# 2_-BATTERY.net
KiCad netlist of a schematic drawn in Altium Designer
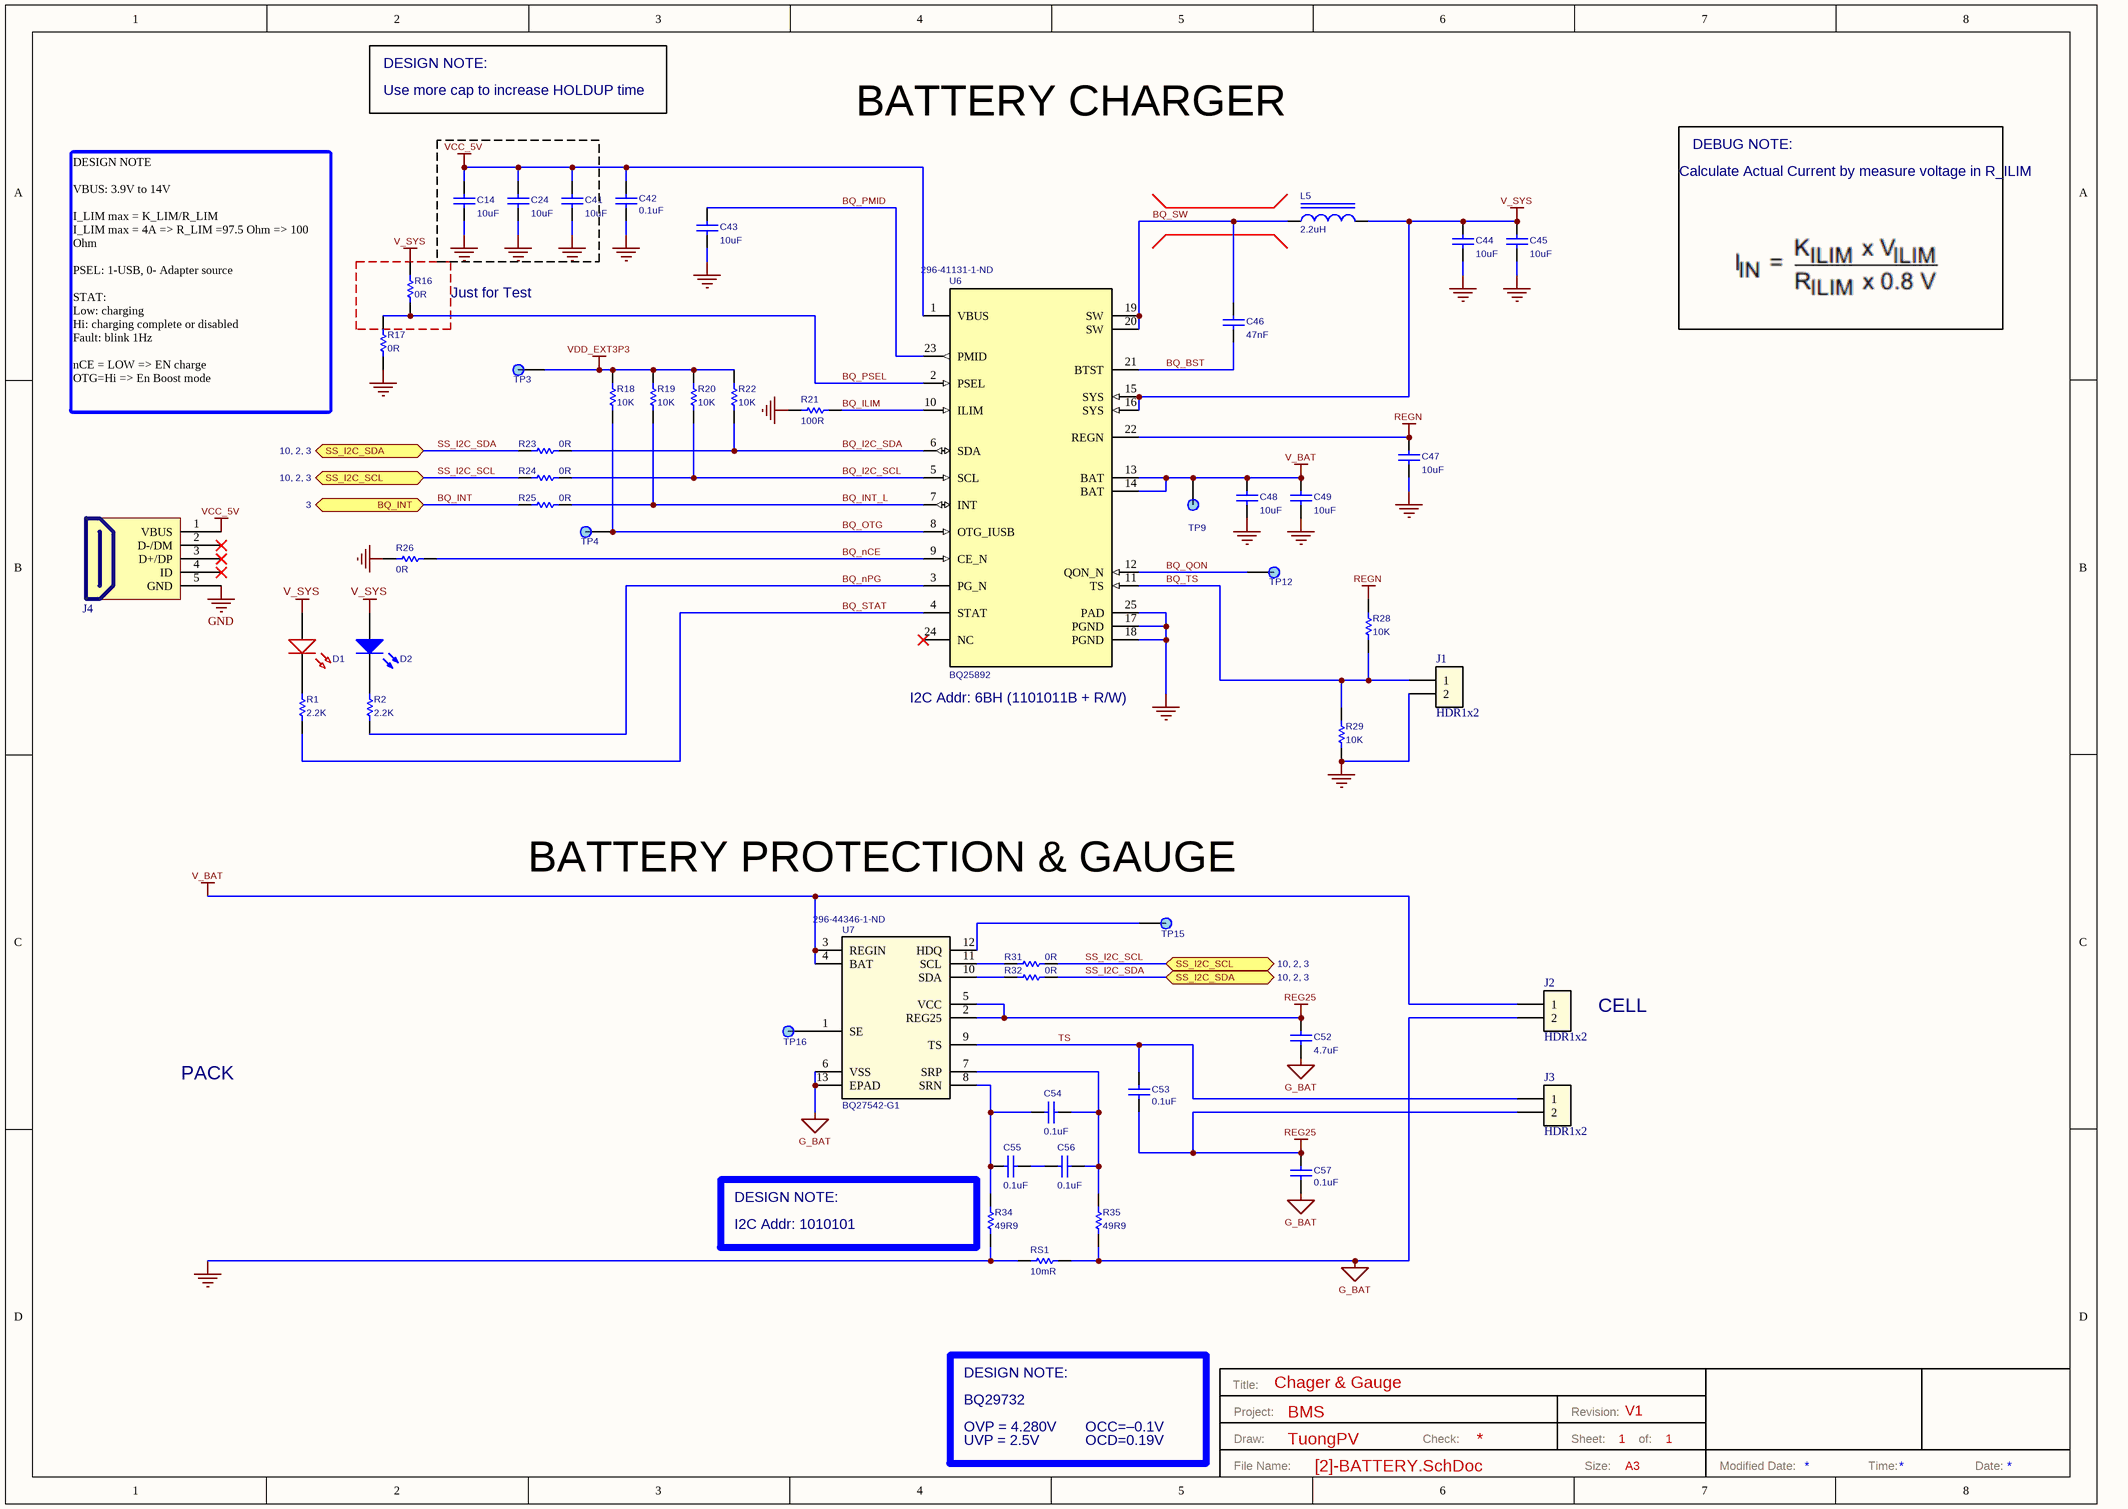
[diagram p0: [2]-BATTERY.SchDoc]

(export (version "E")
  (design (tool "Eeschema 10.0.6"))
  (components
    (comp (ref "C14")
      (value "TMK212BBJ106KG-T")
      (footprint "C0805")
      (description "CAP, CERM, 10uF, 25V, +/-10%, X5R, 0402")
      (fields
        (field (name "LUMI PART") "CAP_10uF_0805")
        (field (name "MANUFACTURER") "Taiyo Yuden")
        (field (name "CAPACITANCE") "10uF")
      )
      (libsource (lib "EFL_AltiumLib") (part "CAP_10uF_0805"))
    )
    (comp (ref "C24")
      (value "TMK212BBJ106KG-T")
      (footprint "C0805")
      (description "CAP, CERM, 10uF, 25V, +/-10%, X5R, 0402")
      (fields
        (field (name "LUMI PART") "CAP_10uF_0805")
        (field (name "MANUFACTURER") "Taiyo Yuden")
        (field (name "CAPACITANCE") "10uF")
      )
      (libsource (lib "EFL_AltiumLib") (part "CAP_10uF_0805"))
    )
    (comp (ref "C41")
      (value "TMK212BBJ106KG-T")
      (footprint "C0805")
      (description "CAP, CERM, 10uF, 25V, +/-10%, X5R, 0402")
      (fields
        (field (name "LUMI PART") "CAP_10uF_0805")
        (field (name "MANUFACTURER") "Taiyo Yuden")
        (field (name "CAPACITANCE") "10uF")
      )
      (libsource (lib "EFL_AltiumLib") (part "CAP_10uF_0805"))
    )
    (comp (ref "C42")
      (value "0603B104K500CT")
      (footprint "C0603")
      (description "CAP, CERM, 0.1uF, 50V, +/-10%, X7R, 0603")
      (fields
        (field (name "LUMI PART") "CAP_104_0603")
        (field (name "MANUFACTURER") "Walsin")
        (field (name "CAPACITANCE") "0.1uF")
      )
      (libsource (lib "LumiLib-CAPACITOR") (part "CERM_0.1uF_0603"))
    )
    (comp (ref "C43")
      (value "TMK212BBJ106KG-T")
      (footprint "C0805")
      (description "CAP, CERM, 10uF, 25V, +/-10%, X5R, 0402")
      (fields
        (field (name "LUMI PART") "CAP_10uF_0805")
        (field (name "MANUFACTURER") "Taiyo Yuden")
        (field (name "CAPACITANCE") "10uF")
      )
      (libsource (lib "EFL_AltiumLib") (part "CAP_10uF_0805"))
    )
    (comp (ref "C44")
      (value "TMK212BBJ106KG-T")
      (footprint "C0805")
      (description "CAP, CERM, 10uF, 25V, +/-10%, X5R, 0402")
      (fields
        (field (name "LUMI PART") "CAP_10uF_0805")
        (field (name "MANUFACTURER") "Taiyo Yuden")
        (field (name "CAPACITANCE") "10uF")
      )
      (libsource (lib "EFL_AltiumLib") (part "CAP_10uF_0805"))
    )
    (comp (ref "C45")
      (value "TMK212BBJ106KG-T")
      (footprint "C0805")
      (description "CAP, CERM, 10uF, 25V, +/-10%, X5R, 0402")
      (fields
        (field (name "LUMI PART") "CAP_10uF_0805")
        (field (name "MANUFACTURER") "Taiyo Yuden")
        (field (name "CAPACITANCE") "10uF")
      )
      (libsource (lib "EFL_AltiumLib") (part "CAP_10uF_0805"))
    )
    (comp (ref "C46")
      (value "GRM155R71C473KA01D")
      (footprint "C0402")
      (description "CAP, CERM, 47nF, 16V, +/-10%, X7R, 0402")
      (fields
        (field (name "LUMI PART") "CAP_47nF_0402")
        (field (name "MANUFACTURER") "Murata")
        (field (name "CAPACITANCE") "47nF")
      )
      (libsource (lib "EFL_GW") (part "CAP_47nF_0402"))
    )
    (comp (ref "C47")
      (value "TMK212BBJ106KG-T")
      (footprint "C0805")
      (description "CAP, CERM, 10uF, 25V, +/-10%, X5R, 0402")
      (fields
        (field (name "LUMI PART") "CAP_10uF_0805")
        (field (name "MANUFACTURER") "Taiyo Yuden")
        (field (name "CAPACITANCE") "10uF")
      )
      (libsource (lib "EFL_AltiumLib") (part "CAP_10uF_0805"))
    )
    (comp (ref "C48")
      (value "TMK212BBJ106KG-T")
      (footprint "C0805")
      (description "CAP, CERM, 10uF, 25V, +/-10%, X5R, 0402")
      (fields
        (field (name "LUMI PART") "CAP_10uF_0805")
        (field (name "MANUFACTURER") "Taiyo Yuden")
        (field (name "CAPACITANCE") "10uF")
      )
      (libsource (lib "EFL_AltiumLib") (part "CAP_10uF_0805"))
    )
    (comp (ref "C49")
      (value "TMK212BBJ106KG-T")
      (footprint "C0805")
      (description "CAP, CERM, 10uF, 25V, +/-10%, X5R, 0402")
      (fields
        (field (name "LUMI PART") "CAP_10uF_0805")
        (field (name "MANUFACTURER") "Taiyo Yuden")
        (field (name "CAPACITANCE") "10uF")
      )
      (libsource (lib "EFL_AltiumLib") (part "CAP_10uF_0805"))
    )
    (comp (ref "C52")
      (value "CL10A475KQ8NNNC")
      (footprint "C0603")
      (description "CAP, CERM, 4.7uF, 6.3V, +/-10%, X5R, 0603")
      (fields
        (field (name "LUMI PART") "CAP_4.7uF_0603")
        (field (name "MANUFACTURER") "Samsung Electro-Mechanics")
        (field (name "CAPACITANCE") "4.7uF")
      )
      (libsource (lib "EFL_GW") (part "CAP_4.7uF_0603"))
    )
    (comp (ref "C53")
      (value "0603B104K500CT")
      (footprint "C0603")
      (description "CAP, CERM, 0.1uF, 50V, +/-10%, X7R, 0603")
      (fields
        (field (name "LUMI PART") "CAP_104_0603")
        (field (name "MANUFACTURER") "Walsin")
        (field (name "CAPACITANCE") "0.1uF")
      )
      (libsource (lib "LumiLib-CAPACITOR") (part "CERM_0.1uF_0603"))
    )
    (comp (ref "C54")
      (value "0603B104K500CT")
      (footprint "C0603")
      (description "CAP, CERM, 0.1uF, 50V, +/-10%, X7R, 0603")
      (fields
        (field (name "LUMI PART") "CAP_104_0603")
        (field (name "MANUFACTURER") "Walsin")
        (field (name "CAPACITANCE") "0.1uF")
      )
      (libsource (lib "LumiLib-CAPACITOR") (part "CERM_0.1uF_0603"))
    )
    (comp (ref "C55")
      (value "0603B104K500CT")
      (footprint "C0603")
      (description "CAP, CERM, 0.1uF, 50V, +/-10%, X7R, 0603")
      (fields
        (field (name "LUMI PART") "CAP_104_0603")
        (field (name "MANUFACTURER") "Walsin")
        (field (name "CAPACITANCE") "0.1uF")
      )
      (libsource (lib "LumiLib-CAPACITOR") (part "CERM_0.1uF_0603"))
    )
    (comp (ref "C56")
      (value "0603B104K500CT")
      (footprint "C0603")
      (description "CAP, CERM, 0.1uF, 50V, +/-10%, X7R, 0603")
      (fields
        (field (name "LUMI PART") "CAP_104_0603")
        (field (name "MANUFACTURER") "Walsin")
        (field (name "CAPACITANCE") "0.1uF")
      )
      (libsource (lib "LumiLib-CAPACITOR") (part "CERM_0.1uF_0603"))
    )
    (comp (ref "C57")
      (value "0603B104K500CT")
      (footprint "C0603")
      (description "CAP, CERM, 0.1uF, 50V, +/-10%, X7R, 0603")
      (fields
        (field (name "LUMI PART") "CAP_104_0603")
        (field (name "MANUFACTURER") "Walsin")
        (field (name "CAPACITANCE") "0.1uF")
      )
      (libsource (lib "LumiLib-CAPACITOR") (part "CERM_0.1uF_0603"))
    )
    (comp (ref "D1")
      (value "LED_WHITE_0603")
      (footprint "LED_BLUE_0603_TOP")
      (description "LED, Mono Colour, WHITE, Top View, SMD 0603")
      (fields
        (field (name "MANUFACTURER") "Everlight")
        (field (name "MANUFACTURER PART NUMBER") "19-218/T1D-CQ2R2TY/3T")
      )
      (libsource (lib "LumiLib-LED") (part "LED_WHITE_0603"))
    )
    (comp (ref "D2")
      (value "LED_BLUE_0603")
      (footprint "LED_BLUE_0603_TOP")
      (description "LED, Mono Colour, BLUE, Top View, SMD 0603")
      (fields
        (field (name "MANUFACTURER") "Everlight")
        (field (name "MANUFACTURER PART NUMBER") "19-217/BHC-ZL1M2RY/3T")
      )
      (libsource (lib "LumiLib-LED") (part "LED_BLUE_0603"))
    )
    (comp (ref "J1")
      (value "HDR1x2")
      (footprint "HDR1x2")
      (description "Header 1x2 2.54mm")
      (libsource (lib "TuongPV") (part "HDR1x2"))
    )
    (comp (ref "J2")
      (value "HDR1x2")
      (footprint "HDR1x2")
      (description "Header 1x2 2.54mm")
      (libsource (lib "TuongPV") (part "HDR1x2"))
    )
    (comp (ref "J3")
      (value "HDR1x2")
      (footprint "HDR1x2")
      (description "Header 1x2 2.54mm")
      (libsource (lib "TuongPV") (part "HDR1x2"))
    )
    (comp (ref "J4")
      (value "microUSB")
      (footprint "MICRO_USB_SMD")
      (description "USB - micro B USB 2.0 Receptacle Connector 5 Position Surface Mount, Right Angle, Horizontal")
      (fields
        (field (name "MANUFACTURER") "Amphenol FCI")
        (field (name "MANUFACTURER PART NUMBER") "10118194-0001LF")
      )
      (libsource (lib "BBiQ_LIB") (part "microUSB"))
    )
    (comp (ref "L5")
      (value "SRP5020TA-2R2M")
      (footprint "SRP5020TA")
      (description "IND,5.7X5.2X1.8MM,2.2UH20%,4.2A")
      (fields (field (name "MANUFACTURER") "Bourns") (field (name "INDUCTANCE") "2.2uH"))
      (libsource (lib "TuongPV") (part "SRP5020TA-2R2M"))
    )
    (comp (ref "R1")
      (value "WR06X222 JTL")
      (footprint "R0603")
      (description "RES, SMD, ThickFilm, 2.2K, 1/10W, 5%, 0603")
      (fields
        (field (name "MANUFACTURER") "Walsin")
        (field (name "LUMI PART") "RES_2.2K_0603")
        (field (name "RESISTANCE (OHMS)") "2.2K")
      )
      (libsource (lib "LumiLib-RESISTOR") (part "RES_2.2K_0603"))
    )
    (comp (ref "R2")
      (value "WR06X222 JTL")
      (footprint "R0603")
      (description "RES, SMD, ThickFilm, 2.2K, 1/10W, 5%, 0603")
      (fields
        (field (name "MANUFACTURER") "Walsin")
        (field (name "LUMI PART") "RES_2.2K_0603")
        (field (name "RESISTANCE (OHMS)") "2.2K")
      )
      (libsource (lib "LumiLib-RESISTOR") (part "RES_2.2K_0603"))
    )
    (comp (ref "R16")
      (value "WR06X000 PTL")
      (footprint "R0603")
      (description "RES, SMD, ThickFilm, 0R, JUMPER, 0603")
      (fields
        (field (name "MANUFACTURER") "Walsin")
        (field (name "LUMI PART") "RES_0R_0603")
        (field (name "RESISTANCE (OHMS)") "0R")
      )
      (libsource (lib "LumiLib-RESISTOR") (part "RES_0R_0603"))
    )
    (comp (ref "R17")
      (value "WR06X000 PTL")
      (footprint "R0603")
      (description "RES, SMD, ThickFilm, 0R, JUMPER, 0603")
      (fields
        (field (name "MANUFACTURER") "Walsin")
        (field (name "LUMI PART") "RES_0R_0603")
        (field (name "RESISTANCE (OHMS)") "0R")
      )
      (libsource (lib "LumiLib-RESISTOR") (part "RES_0R_0603"))
    )
    (comp (ref "R18")
      (value "WR06X103 JTL")
      (footprint "R0603")
      (description "RES, SMD, ThickFilm, 10K, 1/10W, 5%, 0603")
      (fields
        (field (name "MANUFACTURER") "Walsin")
        (field (name "LUMI PART") "RES_10K_0603")
        (field (name "RESISTANCE (OHMS)") "10K")
      )
      (libsource (lib "LumiLib-RESISTOR") (part "RES_10K_0603"))
    )
    (comp (ref "R19")
      (value "WR06X103 JTL")
      (footprint "R0603")
      (description "RES, SMD, ThickFilm, 10K, 1/10W, 5%, 0603")
      (fields
        (field (name "MANUFACTURER") "Walsin")
        (field (name "LUMI PART") "RES_10K_0603")
        (field (name "RESISTANCE (OHMS)") "10K")
      )
      (libsource (lib "LumiLib-RESISTOR") (part "RES_10K_0603"))
    )
    (comp (ref "R20")
      (value "WR06X103 JTL")
      (footprint "R0603")
      (description "RES, SMD, ThickFilm, 10K, 1/10W, 5%, 0603")
      (fields
        (field (name "MANUFACTURER") "Walsin")
        (field (name "LUMI PART") "RES_10K_0603")
        (field (name "RESISTANCE (OHMS)") "10K")
      )
      (libsource (lib "LumiLib-RESISTOR") (part "RES_10K_0603"))
    )
    (comp (ref "R21")
      (value "RC0603FR-07100RL")
      (footprint "R0603")
      (description "RES, SMD, ThickFilm, 100R, 1/10W, 1%, 0603")
      (fields
        (field (name "MANUFACTURER") "Yageo")
        (field (name "LUMI PART") "RES_100R_0603")
        (field (name "RESISTANCE (OHMS)") "100R")
      )
      (libsource (lib "LumiLib-RESISTOR") (part "RES_100R_0603"))
    )
    (comp (ref "R22")
      (value "WR06X103 JTL")
      (footprint "R0603")
      (description "RES, SMD, ThickFilm, 10K, 1/10W, 5%, 0603")
      (fields
        (field (name "MANUFACTURER") "Walsin")
        (field (name "LUMI PART") "RES_10K_0603")
        (field (name "RESISTANCE (OHMS)") "10K")
      )
      (libsource (lib "LumiLib-RESISTOR") (part "RES_10K_0603"))
    )
    (comp (ref "R23")
      (value "WR06X000 PTL")
      (footprint "R0603")
      (description "RES, SMD, ThickFilm, 0R, JUMPER, 0603")
      (fields
        (field (name "MANUFACTURER") "Walsin")
        (field (name "LUMI PART") "RES_0R_0603")
        (field (name "RESISTANCE (OHMS)") "0R")
      )
      (libsource (lib "LumiLib-RESISTOR") (part "RES_0R_0603"))
    )
    (comp (ref "R24")
      (value "WR06X000 PTL")
      (footprint "R0603")
      (description "RES, SMD, ThickFilm, 0R, JUMPER, 0603")
      (fields
        (field (name "MANUFACTURER") "Walsin")
        (field (name "LUMI PART") "RES_0R_0603")
        (field (name "RESISTANCE (OHMS)") "0R")
      )
      (libsource (lib "LumiLib-RESISTOR") (part "RES_0R_0603"))
    )
    (comp (ref "R25")
      (value "WR06X000 PTL")
      (footprint "R0603")
      (description "RES, SMD, ThickFilm, 0R, JUMPER, 0603")
      (fields
        (field (name "MANUFACTURER") "Walsin")
        (field (name "LUMI PART") "RES_0R_0603")
        (field (name "RESISTANCE (OHMS)") "0R")
      )
      (libsource (lib "LumiLib-RESISTOR") (part "RES_0R_0603"))
    )
    (comp (ref "R26")
      (value "WR06X000 PTL")
      (footprint "R0603")
      (description "RES, SMD, ThickFilm, 0R, JUMPER, 0603")
      (fields
        (field (name "MANUFACTURER") "Walsin")
        (field (name "LUMI PART") "RES_0R_0603")
        (field (name "RESISTANCE (OHMS)") "0R")
      )
      (libsource (lib "LumiLib-RESISTOR") (part "RES_0R_0603"))
    )
    (comp (ref "R28")
      (value "WR06X103 JTL")
      (footprint "R0603")
      (description "RES, SMD, ThickFilm, 10K, 1/10W, 5%, 0603")
      (fields
        (field (name "MANUFACTURER") "Walsin")
        (field (name "LUMI PART") "RES_10K_0603")
        (field (name "RESISTANCE (OHMS)") "10K")
      )
      (libsource (lib "LumiLib-RESISTOR") (part "RES_10K_0603"))
    )
    (comp (ref "R29")
      (value "WR06X103 JTL")
      (footprint "R0603")
      (description "RES, SMD, ThickFilm, 10K, 1/10W, 5%, 0603")
      (fields
        (field (name "MANUFACTURER") "Walsin")
        (field (name "LUMI PART") "RES_10K_0603")
        (field (name "RESISTANCE (OHMS)") "10K")
      )
      (libsource (lib "LumiLib-RESISTOR") (part "RES_10K_0603"))
    )
    (comp (ref "R31")
      (value "WR06X000 PTL")
      (footprint "R0603")
      (description "RES, SMD, ThickFilm, 0R, JUMPER, 0603")
      (fields
        (field (name "MANUFACTURER") "Walsin")
        (field (name "LUMI PART") "RES_0R_0603")
        (field (name "RESISTANCE (OHMS)") "0R")
      )
      (libsource (lib "LumiLib-RESISTOR") (part "RES_0R_0603"))
    )
    (comp (ref "R32")
      (value "WR06X000 PTL")
      (footprint "R0603")
      (description "RES, SMD, ThickFilm, 0R, JUMPER, 0603")
      (fields
        (field (name "MANUFACTURER") "Walsin")
        (field (name "LUMI PART") "RES_0R_0603")
        (field (name "RESISTANCE (OHMS)") "0R")
      )
      (libsource (lib "LumiLib-RESISTOR") (part "RES_0R_0603"))
    )
    (comp (ref "R34")
      (value "RC0603FR-0749R9L")
      (footprint "R0603")
      (description "RES, SMD, ThickFilm, 49R9, 1/10W, 1%, 0603")
      (fields
        (field (name "MANUFACTURER") "Yageo")
        (field (name "LUMI PART") "RES_49R9_0603")
        (field (name "RESISTANCE (OHMS)") "49R9")
      )
      (libsource (lib "LumiLib-RESISTOR") (part "RES_49R9_0603"))
    )
    (comp (ref "R35")
      (value "RC0603FR-0749R9L")
      (footprint "R0603")
      (description "RES, SMD, ThickFilm, 49R9, 1/10W, 1%, 0603")
      (fields
        (field (name "MANUFACTURER") "Yageo")
        (field (name "LUMI PART") "RES_49R9_0603")
        (field (name "RESISTANCE (OHMS)") "49R9")
      )
      (libsource (lib "LumiLib-RESISTOR") (part "RES_49R9_0603"))
    )
    (comp (ref "RS1")
      (value "PA2512FKF7W0R001E")
      (footprint "R2512L")
      (description "RES, SMD, Current Sense Resistors, 1mOhms, 2W, 1%, 2512")
      (fields
        (field (name "MANUFACTURER") "Yageo")
        (field (name "LUMI PART") "RES_1mR_2512")
        (field (name "RESISTANCE (OHMS)") "10mR")
      )
      (libsource (lib "EFL_AltiumLib") (part "RES_1mR_2512"))
    )
    (comp (ref "TP3")
      (value "TestPoint")
      (footprint "TESTPOINT")
      (fields (field (name "PUBLISHER") "LUMIVN"))
      (libsource (lib "LumiLib-Other") (part "TestPoint"))
    )
    (comp (ref "TP4")
      (value "TestPoint")
      (footprint "TESTPOINT")
      (fields (field (name "PUBLISHER") "LUMIVN"))
      (libsource (lib "LumiLib-Other") (part "TestPoint"))
    )
    (comp (ref "TP9")
      (value "TestPoint")
      (footprint "TESTPOINT")
      (fields (field (name "PUBLISHER") "LUMIVN"))
      (libsource (lib "LumiLib-Other") (part "TestPoint"))
    )
    (comp (ref "TP12")
      (value "TestPoint")
      (footprint "TESTPOINT")
      (fields (field (name "PUBLISHER") "LUMIVN"))
      (libsource (lib "LumiLib-Other") (part "TestPoint"))
    )
    (comp (ref "TP15")
      (value "TestPoint")
      (footprint "TESTPOINT")
      (fields (field (name "PUBLISHER") "LUMIVN"))
      (libsource (lib "LumiLib-Other") (part "TestPoint"))
    )
    (comp (ref "TP16")
      (value "TestPoint")
      (footprint "TESTPOINT")
      (fields (field (name "PUBLISHER") "LUMIVN"))
      (libsource (lib "LumiLib-Other") (part "TestPoint"))
    )
    (comp (ref "U6")
      (value "BQ25892")
      (footprint "QFN24-4x4x0.8-0.5")
      (description "1S 5A Fast Charger MaxCharge")
      (fields
        (field (name "SUPPLIER PART NUMBER 1") "296-41131-1-ND")
        (field (name "MANUFACTURER") "Texas Instruments")
        (field (name "MANUFACTURER PART NUMBER") "BQ25892RTWT")
      )
      (libsource (lib "TuongPV") (part "BQ25892"))
    )
    (comp (ref "U7")
      (value "BQ27542-G1")
      (footprint "BQ27542DRZR-G1")
      (fields
        (field (name "MANUFACTURER") "Texas Instruments")
        (field (name "MANUFACTURER PART NUMBER") "BQ27541DRZR-G1")
        (field (name "SUPPLIER PART NUMBER 2") "296-44346-1-ND")
      )
      (libsource (lib "TuongPV") (part "BQ27542-G1"))
    )
  )
  (nets
    (net (code "1") (name "/BQ_BST") (class "Default")
      (node (ref "C46") (pin "1") (pinfunction "1_1") (pintype "passive"))
      (node (ref "U6") (pin "21") (pinfunction "BTST_21") (pintype "power_in"))
    )
    (net (code "2") (name "/BQ_I2C_SCL") (class "Default")
      (node (ref "R20") (pin "2") (pinfunction "2_2") (pintype "passive"))
      (node (ref "R24") (pin "1") (pinfunction "1_1") (pintype "passive"))
      (node (ref "U6") (pin "5") (pinfunction "SCL_5") (pintype "input"))
    )
    (net (code "3") (name "/BQ_I2C_SDA") (class "Default")
      (node (ref "R22") (pin "2") (pinfunction "2_2") (pintype "passive"))
      (node (ref "R23") (pin "1") (pinfunction "1_1") (pintype "passive"))
      (node (ref "U6") (pin "6") (pinfunction "SDA_6") (pintype "bidirectional"))
    )
    (net (code "4") (name "/BQ_ILIM") (class "Default")
      (node (ref "R21") (pin "1") (pinfunction "1_1") (pintype "passive"))
      (node (ref "U6") (pin "10") (pinfunction "ILIM_10") (pintype "input"))
    )
    (net (code "5") (name "/BQ_INT") (class "Default")
      (node (ref "R25") (pin "2") (pinfunction "2_2") (pintype "passive"))
    )
    (net (code "6") (name "/BQ_INT_L") (class "Default")
      (node (ref "R19") (pin "2") (pinfunction "2_2") (pintype "passive"))
      (node (ref "R25") (pin "1") (pinfunction "1_1") (pintype "passive"))
      (node (ref "U6") (pin "7") (pinfunction "INT_7") (pintype "bidirectional"))
    )
    (net (code "7") (name "/BQ_OTG") (class "Default")
      (node (ref "R18") (pin "2") (pinfunction "2_2") (pintype "passive"))
      (node (ref "TP4") (pin "1") (pinfunction "1_1") (pintype "passive"))
      (node (ref "U6") (pin "8") (pinfunction "OTG_IUSB_8") (pintype "input"))
    )
    (net (code "8") (name "/BQ_PMID") (class "Default")
      (node (ref "C43") (pin "2") (pinfunction "2_2") (pintype "passive"))
      (node (ref "U6") (pin "23") (pinfunction "PMID_23") (pintype "output"))
    )
    (net (code "9") (name "/BQ_PSEL") (class "Default")
      (node (ref "R16") (pin "2") (pinfunction "2_2") (pintype "passive"))
      (node (ref "R17") (pin "1") (pinfunction "1_1") (pintype "passive"))
      (node (ref "U6") (pin "2") (pinfunction "PSEL_2") (pintype "input"))
    )
    (net (code "10") (name "/BQ_QON") (class "Default")
      (node (ref "TP12") (pin "1") (pinfunction "1_1") (pintype "passive"))
      (node (ref "U6") (pin "12") (pinfunction "QON_N_12") (pintype "input"))
    )
    (net (code "11") (name "/BQ_STAT") (class "Default")
      (node (ref "R1") (pin "1") (pinfunction "1_1") (pintype "passive"))
      (node (ref "U6") (pin "4") (pinfunction "STAT_4") (pintype "open_collector"))
    )
    (net (code "12") (name "/BQ_SW") (class "Default")
      (node (ref "C46") (pin "2") (pinfunction "2_2") (pintype "passive"))
      (node (ref "L5") (pin "1") (pinfunction "1_1") (pintype "passive"))
      (node (ref "U6") (pin "19") (pinfunction "SW_19") (pintype "power_in"))
      (node (ref "U6") (pin "20") (pinfunction "SW_20") (pintype "power_in"))
    )
    (net (code "13") (name "/BQ_TS") (class "Default")
      (node (ref "J1") (pin "1") (pinfunction "1_1") (pintype "passive"))
      (node (ref "R28") (pin "2") (pinfunction "2_2") (pintype "passive"))
      (node (ref "R29") (pin "1") (pinfunction "1_1") (pintype "passive"))
      (node (ref "U6") (pin "11") (pinfunction "TS_11") (pintype "input"))
    )
    (net (code "14") (name "/BQ_nCE") (class "Default")
      (node (ref "R26") (pin "2") (pinfunction "2_2") (pintype "passive"))
      (node (ref "U6") (pin "9") (pinfunction "CE_N_9") (pintype "input"))
    )
    (net (code "15") (name "/BQ_nPG") (class "Default")
      (node (ref "R2") (pin "1") (pinfunction "1_1") (pintype "passive"))
      (node (ref "U6") (pin "3") (pinfunction "PG_N_3") (pintype "open_collector"))
    )
    (net (code "16") (name "/SS_I2C_SCL") (class "Default")
      (node (ref "R24") (pin "2") (pinfunction "2_2") (pintype "passive"))
      (node (ref "R31") (pin "1") (pinfunction "1_1") (pintype "passive"))
    )
    (net (code "17") (name "/SS_I2C_SDA") (class "Default")
      (node (ref "R23") (pin "2") (pinfunction "2_2") (pintype "passive"))
      (node (ref "R32") (pin "1") (pinfunction "1_1") (pintype "passive"))
    )
    (net (code "18") (name "/TS") (class "Default")
      (node (ref "C53") (pin "2") (pinfunction "2_2") (pintype "passive"))
      (node (ref "J3") (pin "1") (pinfunction "1_1") (pintype "passive"))
      (node (ref "U7") (pin "9") (pinfunction "TS_9") (pintype "passive"))
    )
    (net (code "19") (name "GND") (class "Default")
      (node (ref "C14") (pin "1") (pinfunction "1_1") (pintype "passive"))
      (node (ref "C24") (pin "1") (pinfunction "1_1") (pintype "passive"))
      (node (ref "C41") (pin "1") (pinfunction "1_1") (pintype "passive"))
      (node (ref "C42") (pin "1") (pinfunction "1_1") (pintype "passive"))
      (node (ref "C43") (pin "1") (pinfunction "1_1") (pintype "passive"))
      (node (ref "C44") (pin "1") (pinfunction "1_1") (pintype "passive"))
      (node (ref "C45") (pin "1") (pinfunction "1_1") (pintype "passive"))
      (node (ref "C47") (pin "1") (pinfunction "1_1") (pintype "passive"))
      (node (ref "C48") (pin "1") (pinfunction "1_1") (pintype "passive"))
      (node (ref "C49") (pin "1") (pinfunction "1_1") (pintype "passive"))
      (node (ref "J1") (pin "2") (pinfunction "2_2") (pintype "passive"))
      (node (ref "J4") (pin "5") (pinfunction "GND_5") (pintype "passive"))
      (node (ref "R17") (pin "2") (pinfunction "2_2") (pintype "passive"))
      (node (ref "R21") (pin "2") (pinfunction "2_2") (pintype "passive"))
      (node (ref "R26") (pin "1") (pinfunction "1_1") (pintype "passive"))
      (node (ref "R29") (pin "2") (pinfunction "2_2") (pintype "passive"))
      (node (ref "R34") (pin "1") (pinfunction "1_1") (pintype "passive"))
      (node (ref "RS1") (pin "1") (pinfunction "1_1") (pintype "passive"))
      (node (ref "U6") (pin "17") (pinfunction "PGND_17") (pintype "power_in"))
      (node (ref "U6") (pin "18") (pinfunction "PGND_18") (pintype "power_in"))
      (node (ref "U6") (pin "25") (pinfunction "PAD_25") (pintype "power_in"))
    )
    (net (code "20") (name "G_BAT") (class "Default")
      (node (ref "C52") (pin "1") (pinfunction "1_1") (pintype "passive"))
      (node (ref "C57") (pin "1") (pinfunction "1_1") (pintype "passive"))
      (node (ref "J2") (pin "2") (pinfunction "2_2") (pintype "passive"))
      (node (ref "R35") (pin "1") (pinfunction "1_1") (pintype "passive"))
      (node (ref "RS1") (pin "2") (pinfunction "2_2") (pintype "passive"))
      (node (ref "U7") (pin "13") (pinfunction "EPAD_13") (pintype "passive"))
      (node (ref "U7") (pin "6") (pinfunction "VSS_6") (pintype "passive"))
    )
    (net (code "21") (name "Net-(C55-Pad1)") (class "Default")
      (node (ref "C55") (pin "1") (pinfunction "1_1") (pintype "passive"))
      (node (ref "C56") (pin "2") (pinfunction "2_2") (pintype "passive"))
    )
    (net (code "22") (name "Net-(D1-K)") (class "Default")
      (node (ref "D1") (pin "2") (pinfunction "K_2") (pintype "passive"))
      (node (ref "R1") (pin "2") (pinfunction "2_2") (pintype "passive"))
    )
    (net (code "23") (name "Net-(D2-K)") (class "Default")
      (node (ref "D2") (pin "2") (pinfunction "K_2") (pintype "passive"))
      (node (ref "R2") (pin "2") (pinfunction "2_2") (pintype "passive"))
    )
    (net (code "24") (name "Net-(U7-HDQ)") (class "Default")
      (node (ref "TP15") (pin "1") (pinfunction "1_1") (pintype "passive"))
      (node (ref "U7") (pin "12") (pinfunction "HDQ_12") (pintype "passive"))
    )
    (net (code "25") (name "Net-(U7-SCL)") (class "Default")
      (node (ref "R31") (pin "2") (pinfunction "2_2") (pintype "passive"))
      (node (ref "U7") (pin "11") (pinfunction "SCL_11") (pintype "passive"))
    )
    (net (code "26") (name "Net-(U7-SDA)") (class "Default")
      (node (ref "R32") (pin "2") (pinfunction "2_2") (pintype "passive"))
      (node (ref "U7") (pin "10") (pinfunction "SDA_10") (pintype "passive"))
    )
    (net (code "27") (name "Net-(U7-SE)") (class "Default")
      (node (ref "TP16") (pin "1") (pinfunction "1_1") (pintype "passive"))
      (node (ref "U7") (pin "1") (pinfunction "SE_1") (pintype "passive"))
    )
    (net (code "28") (name "Net-(U7-SRN)") (class "Default")
      (node (ref "C54") (pin "2") (pinfunction "2_2") (pintype "passive"))
      (node (ref "C55") (pin "2") (pinfunction "2_2") (pintype "passive"))
      (node (ref "R34") (pin "2") (pinfunction "2_2") (pintype "passive"))
      (node (ref "U7") (pin "8") (pinfunction "SRN_8") (pintype "passive"))
    )
    (net (code "29") (name "Net-(U7-SRP)") (class "Default")
      (node (ref "C54") (pin "1") (pinfunction "1_1") (pintype "passive"))
      (node (ref "C56") (pin "1") (pinfunction "1_1") (pintype "passive"))
      (node (ref "R35") (pin "2") (pinfunction "2_2") (pintype "passive"))
      (node (ref "U7") (pin "7") (pinfunction "SRP_7") (pintype "passive"))
    )
    (net (code "30") (name "REG25") (class "Default")
      (node (ref "C52") (pin "2") (pinfunction "2_2") (pintype "passive"))
      (node (ref "C53") (pin "1") (pinfunction "1_1") (pintype "passive"))
      (node (ref "C57") (pin "2") (pinfunction "2_2") (pintype "passive"))
      (node (ref "J3") (pin "2") (pinfunction "2_2") (pintype "passive"))
      (node (ref "U7") (pin "2") (pinfunction "REG25_2") (pintype "passive"))
      (node (ref "U7") (pin "5") (pinfunction "VCC_5") (pintype "passive"))
    )
    (net (code "31") (name "REGN") (class "Default")
      (node (ref "C47") (pin "2") (pinfunction "2_2") (pintype "passive"))
      (node (ref "R28") (pin "1") (pinfunction "1_1") (pintype "passive"))
      (node (ref "U6") (pin "22") (pinfunction "REGN_22") (pintype "power_in"))
    )
    (net (code "32") (name "VCC_5V") (class "Default")
      (node (ref "C14") (pin "2") (pinfunction "2_2") (pintype "passive"))
      (node (ref "C24") (pin "2") (pinfunction "2_2") (pintype "passive"))
      (node (ref "C41") (pin "2") (pinfunction "2_2") (pintype "passive"))
      (node (ref "C42") (pin "2") (pinfunction "2_2") (pintype "passive"))
      (node (ref "J4") (pin "1") (pinfunction "VBUS_1") (pintype "passive"))
      (node (ref "U6") (pin "1") (pinfunction "VBUS_1") (pintype "power_in"))
    )
    (net (code "33") (name "VDD_EXT3P3") (class "Default")
      (node (ref "R18") (pin "1") (pinfunction "1_1") (pintype "passive"))
      (node (ref "R19") (pin "1") (pinfunction "1_1") (pintype "passive"))
      (node (ref "R20") (pin "1") (pinfunction "1_1") (pintype "passive"))
      (node (ref "R22") (pin "1") (pinfunction "1_1") (pintype "passive"))
      (node (ref "TP3") (pin "1") (pinfunction "1_1") (pintype "passive"))
    )
    (net (code "34") (name "V_BAT") (class "Default")
      (node (ref "C48") (pin "2") (pinfunction "2_2") (pintype "passive"))
      (node (ref "C49") (pin "2") (pinfunction "2_2") (pintype "passive"))
      (node (ref "J2") (pin "1") (pinfunction "1_1") (pintype "passive"))
      (node (ref "TP9") (pin "1") (pinfunction "1_1") (pintype "passive"))
      (node (ref "U6") (pin "13") (pinfunction "BAT_13") (pintype "power_in"))
      (node (ref "U6") (pin "14") (pinfunction "BAT_14") (pintype "power_in"))
      (node (ref "U7") (pin "3") (pinfunction "REGIN_3") (pintype "passive"))
      (node (ref "U7") (pin "4") (pinfunction "BAT_4") (pintype "passive"))
    )
    (net (code "35") (name "V_SYS") (class "Default")
      (node (ref "C44") (pin "2") (pinfunction "2_2") (pintype "passive"))
      (node (ref "C45") (pin "2") (pinfunction "2_2") (pintype "passive"))
      (node (ref "D1") (pin "1") (pinfunction "A_1") (pintype "passive"))
      (node (ref "D2") (pin "1") (pinfunction "A_1") (pintype "passive"))
      (node (ref "L5") (pin "2") (pinfunction "2_2") (pintype "passive"))
      (node (ref "R16") (pin "1") (pinfunction "1_1") (pintype "passive"))
      (node (ref "U6") (pin "15") (pinfunction "SYS_15") (pintype "input"))
      (node (ref "U6") (pin "16") (pinfunction "SYS_16") (pintype "input"))
    )
    (net (code "36") (name "unconnected-(J4-D+{slash}DP-Pad3)") (class "Default")
      (node (ref "J4") (pin "3") (pinfunction "D+/DP_3") (pintype "passive+no_connect"))
    )
    (net (code "37") (name "unconnected-(J4-D-{slash}DM-Pad2)") (class "Default")
      (node (ref "J4") (pin "2") (pinfunction "D-/DM_2") (pintype "passive+no_connect"))
    )
    (net (code "38") (name "unconnected-(J4-ID-Pad4)") (class "Default")
      (node (ref "J4") (pin "4") (pinfunction "ID_4") (pintype "passive+no_connect"))
    )
    (net (code "39") (name "unconnected-(U6-NC-Pad24)") (class "Default")
      (node (ref "U6") (pin "24") (pinfunction "NC_24") (pintype "passive+no_connect"))
    )
  )
)
